# NIC145_Noise_Gate_Schematic.net
KiCad netlist of a schematic drawn in Altium Designer
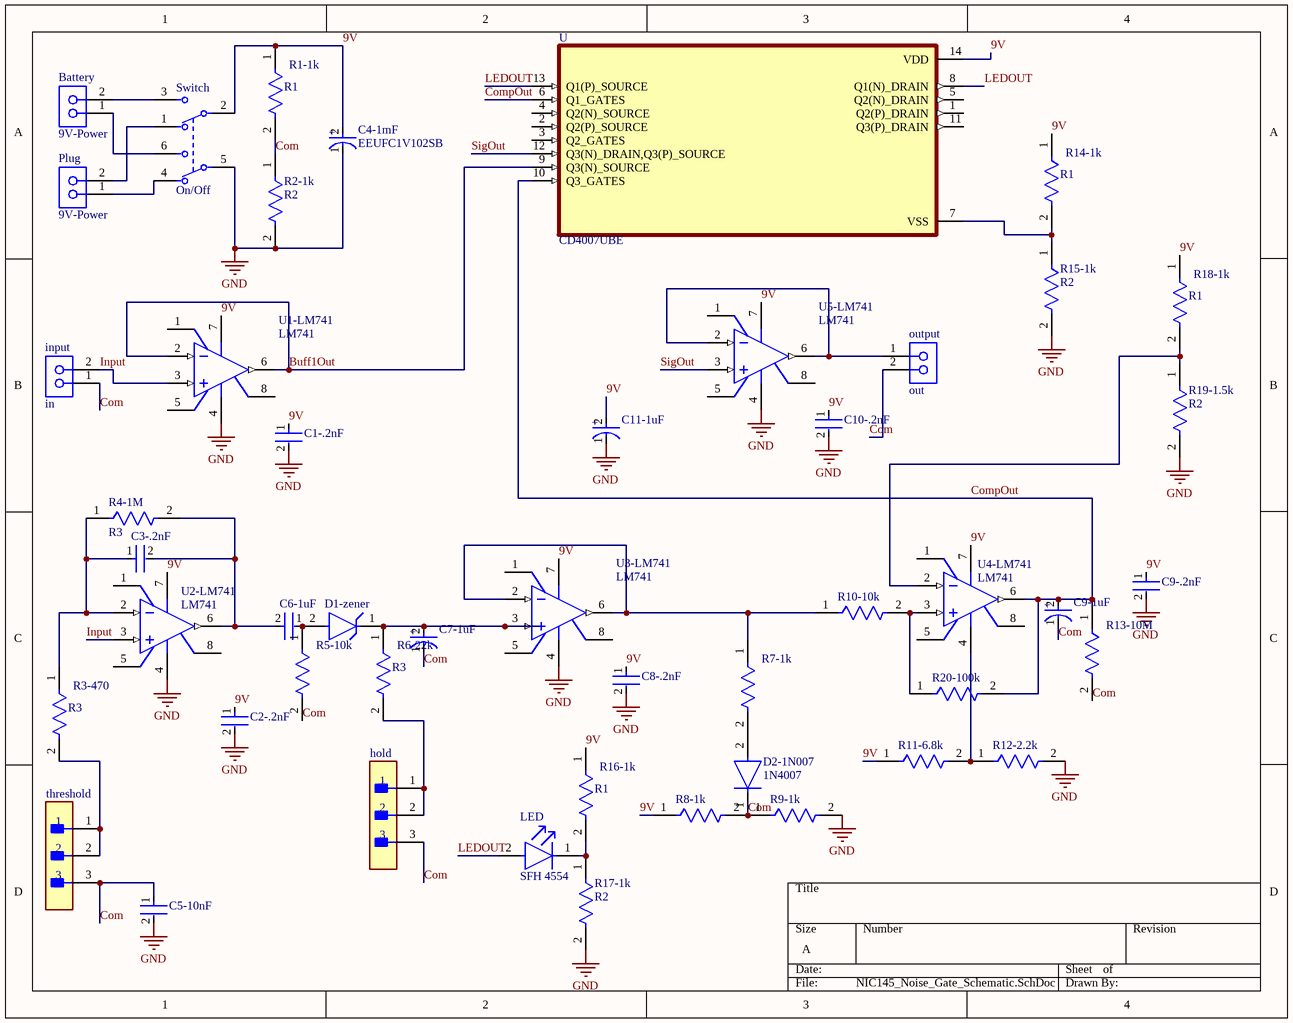
[diagram p0: NIC145_Noise_Gate_Schematic.SchDoc]

(export (version "E")
  (design (tool "Eeschema 10.0.6"))
  (components
    (comp (ref "Battery")
      (value "9V-Power")
      (footprint "SMTC-SSW-102-02-X-S")
      (description "SQ Post Socket, Through-hole, Vertical, -55 to 105 degC, 2.54 mm Pitch, 2-Pin, Female, RoHS")
      (fields (field (name "MANUFACTURER") "Samtec") (field (name "PARTNUMBER") "SSW-102-02-T-S"))
      (libsource (lib "Altium Content Vault") (part "SMTC-SSW-102-02-X-S-X"))
    )
    (comp (ref "C1-.2nF")
      (value "~")
      (footprint "FP-565R30GASS33-MFG")
      (description "565R30GASS33 33nF 3 kV dc Ceramic Single Layer Capacitor; Z5U Dielectric Radial 565R Series")
      (fields (field (name "VOLTAGE") "3kV") (field (name "TOLERANCE") "20%"))
      (libsource (lib "Altium Content Vault") (part "02cd4be3c70576c341d710602a673aa"))
    )
    (comp (ref "C2-.2nF")
      (value "~")
      (footprint "FP-565R30GASS33-MFG")
      (description "565R30GASS33 33nF 3 kV dc Ceramic Single Layer Capacitor; Z5U Dielectric Radial 565R Series")
      (fields (field (name "VOLTAGE") "3kV") (field (name "TOLERANCE") "20%"))
      (libsource (lib "Altium Content Vault") (part "02cd4be3c70576c341d710602a673aa"))
    )
    (comp (ref "C3-.2nF")
      (value "~")
      (footprint "FP-565R30GASS33-MFG")
      (description "565R30GASS33 33nF 3 kV dc Ceramic Single Layer Capacitor; Z5U Dielectric Radial 565R Series")
      (fields (field (name "VOLTAGE") "3kV") (field (name "TOLERANCE") "20%"))
      (libsource (lib "Altium Content Vault") (part "02cd4be3c70576c341d710602a673aa"))
    )
    (comp (ref "C4-1mF")
      (value "EEUFC1V102SB")
      (footprint "FP-RAD-TH-D_16_0_5-L_20_2-MFG")
      (description "Aluminum Electrolytic Capacitors (Radial Lead Type) AEC-Q200 Qualified 1000uF ±20% 35V")
      (fields (field (name "TOLERANCE") "20%"))
      (libsource (lib "Altium Content Vault") (part "203bc49f2ac43e59fd269a8c329ed05"))
    )
    (comp (ref "C5-10nF")
      (value "ECWF4754JL")
      (footprint "FP-ECWF4754JL-MFG")
      (description "CAP FILM 0.75UF 5% 400VDC RADIAL")
      (fields
        (field (name "TOLERANCE") "5%")
        (field (name "OCTOPART") "https://octopart.com/ecw-f4754jl-panasonic-39488642")
      )
      (libsource (lib "Altium Content Vault") (part "b4654b650e69147ec39a6b967a45e02"))
    )
    (comp (ref "C6-1uF")
      (value "PHE844RR7100MR06L2")
      (footprint "FP-PHE844RR7100MR06L2-MFG")
      (description "CAP FILM 1UF 20% 1KVDC RADIAL")
      (fields (field (name "TOLERANCE") "20%"))
      (libsource (lib "Altium Content Vault") (part "236180d848d6139a670b325ea6854c9"))
    )
    (comp (ref "C7-1uF")
      (value "ECA-2CHG010I")
      (footprint "FP-ECA-2CHG010I-MFG")
      (description "CAP ALUM 1UF 20% 160V RADIAL")
      (fields (field (name "TOLERANCE") "20%"))
      (libsource (lib "Altium Content Vault") (part "a00bbbee19879c290e62620ae7e47b1"))
    )
    (comp (ref "C8-.2nF")
      (value "~")
      (footprint "FP-565R30GASS33-MFG")
      (description "565R30GASS33 33nF 3 kV dc Ceramic Single Layer Capacitor; Z5U Dielectric Radial 565R Series")
      (fields (field (name "VOLTAGE") "3kV") (field (name "TOLERANCE") "20%"))
      (libsource (lib "Altium Content Vault") (part "02cd4be3c70576c341d710602a673aa"))
    )
    (comp (ref "C9-.2nF")
      (value "~")
      (footprint "FP-565R30GASS33-MFG")
      (description "565R30GASS33 33nF 3 kV dc Ceramic Single Layer Capacitor; Z5U Dielectric Radial 565R Series")
      (fields (field (name "VOLTAGE") "3kV") (field (name "TOLERANCE") "20%"))
      (libsource (lib "Altium Content Vault") (part "02cd4be3c70576c341d710602a673aa"))
    )
    (comp (ref "C9-1uF")
      (value "ECA-2CHG010I")
      (footprint "FP-ECA-2CHG010I-MFG")
      (description "CAP ALUM 1UF 20% 160V RADIAL")
      (fields (field (name "TOLERANCE") "20%"))
      (libsource (lib "Altium Content Vault") (part "a00bbbee19879c290e62620ae7e47b1"))
    )
    (comp (ref "C10-.2nF")
      (value "~")
      (footprint "FP-565R30GASS33-MFG")
      (description "565R30GASS33 33nF 3 kV dc Ceramic Single Layer Capacitor; Z5U Dielectric Radial 565R Series")
      (fields (field (name "VOLTAGE") "3kV") (field (name "TOLERANCE") "20%"))
      (libsource (lib "Altium Content Vault") (part "02cd4be3c70576c341d710602a673aa"))
    )
    (comp (ref "C11-1uF")
      (value "ECA-2CHG010I")
      (footprint "FP-ECA-2CHG010I-MFG")
      (description "CAP ALUM 1UF 20% 160V RADIAL")
      (fields (field (name "TOLERANCE") "20%"))
      (libsource (lib "Altium Content Vault") (part "a00bbbee19879c290e62620ae7e47b1"))
    )
    (comp (ref "D1-zener")
      (value "1N5242BTR")
      (footprint "FP-017AG-MFG")
      (description "1N5242BTR 1N5242 Series 500 mW 12 V 200 mA Through Hole Zener Diode - DO-35")
      (fields (field (name "TOLERANCE") "5%"))
      (libsource (lib "Altium Content Vault") (part "f813f71cba58e380607f5dd3caf9714"))
    )
    (comp (ref "D2-1N007")
      (value "1N4007")
      (footprint "FP-1N4007-MFG")
      (description "Rectifier diode 1000 V 1 A DO-41, ,")
      (fields
        (field (name "MANUFACTURER") "Diotec")
        (field (name "OCTOPART") "https://octopart.com/1n4007-diotec-4040411")
      )
      (libsource (lib "Altium Content Vault") (part "d7152d700b627762746794eb795d46e"))
    )
    (comp (ref "hold")
      (value "~")
      (footprint "FP-641966-1-MFG")
      (description "CONN HEADER VERT 3POS 6.35MM")
      (fields
        (field (name "MANUFACTURER PART NUMBER") "641966-1")
        (field (name "OCTOPART") "https://octopart.com/641966-1-te+connectivity-46507674")
      )
      (libsource (lib "Altium Content Vault") (part "0d3f023dd272f625e17a2be33dea85f"))
    )
    (comp (ref "input")
      (value "in")
      (footprint "SMTC-SSW-102-02-X-S")
      (description "SQ Post Socket, Through-hole, Vertical, -55 to 105 degC, 2.54 mm Pitch, 2-Pin, Female, RoHS")
      (fields (field (name "MANUFACTURER") "Samtec") (field (name "PARTNUMBER") "SSW-102-02-T-S"))
      (libsource (lib "Altium Content Vault") (part "SMTC-SSW-102-02-X-S-X"))
    )
    (comp (ref "LED")
      (value "SFH 4554")
      (footprint "FP-SFH_4554-MFG")
      (description "EMITTER IR 850NM")
      (fields
        (field (name "OCTOPART") "https://octopart.com/sfh+4554-osram+opto-55819455")
        (field (name "MANUFACTURER") "Osram Opto")
      )
      (libsource (lib "Altium Content Vault") (part "8706943c75ba83719d021d2fdc84c58"))
    )
    (comp (ref "output")
      (value "out")
      (footprint "SMTC-SSW-102-02-X-S")
      (description "SQ Post Socket, Through-hole, Vertical, -55 to 105 degC, 2.54 mm Pitch, 2-Pin, Female, RoHS")
      (fields (field (name "MANUFACTURER") "Samtec") (field (name "PARTNUMBER") "SSW-102-02-T-S"))
      (libsource (lib "Altium Content Vault") (part "SMTC-SSW-102-02-X-S-X"))
    )
    (comp (ref "Plug")
      (value "9V-Power")
      (footprint "SMTC-SSW-102-02-X-S")
      (description "SQ Post Socket, Through-hole, Vertical, -55 to 105 degC, 2.54 mm Pitch, 2-Pin, Female, RoHS")
      (fields (field (name "MANUFACTURER") "Samtec") (field (name "PARTNUMBER") "SSW-102-02-T-S"))
      (libsource (lib "Altium Content Vault") (part "SMTC-SSW-102-02-X-S-X"))
    )
    (comp (ref "R1-1k")
      (value "R1")
      (footprint "FP-MRS25-MFG")
      (description "RES 1K OHM 0.6W 1% AXIAL")
      (fields (field (name "TOLERANCE") "1%"))
      (libsource (lib "Altium Content Vault") (part "1029c3af85768c4190bb7ad29bc67b5"))
    )
    (comp (ref "R2-1k")
      (value "R2")
      (footprint "FP-MRS25-MFG")
      (description "RES 1K OHM 0.6W 1% AXIAL")
      (fields (field (name "TOLERANCE") "1%"))
      (libsource (lib "Altium Content Vault") (part "1029c3af85768c4190bb7ad29bc67b5"))
    )
    (comp (ref "R3-470")
      (value "R3")
      (footprint "FP-MRS25-MFG")
      (description "RES 1K OHM 0.6W 1% AXIAL")
      (fields (field (name "TOLERANCE") "1%"))
      (libsource (lib "Altium Content Vault") (part "1029c3af85768c4190bb7ad29bc67b5"))
    )
    (comp (ref "R4-1M")
      (value "R3")
      (footprint "FP-MRS25-MFG")
      (description "RES 1K OHM 0.6W 1% AXIAL")
      (fields (field (name "TOLERANCE") "1%"))
      (libsource (lib "Altium Content Vault") (part "1029c3af85768c4190bb7ad29bc67b5"))
    )
    (comp (ref "R5-10k")
      (value "R3")
      (footprint "FP-MRS25-MFG")
      (description "RES 1K OHM 0.6W 1% AXIAL")
      (fields (field (name "TOLERANCE") "1%"))
      (libsource (lib "Altium Content Vault") (part "1029c3af85768c4190bb7ad29bc67b5"))
    )
    (comp (ref "R6-22k")
      (value "R3")
      (footprint "FP-MRS25-MFG")
      (description "RES 1K OHM 0.6W 1% AXIAL")
      (fields (field (name "TOLERANCE") "1%"))
      (libsource (lib "Altium Content Vault") (part "1029c3af85768c4190bb7ad29bc67b5"))
    )
    (comp (ref "R7-1k")
      (value "R3")
      (footprint "FP-MRS25-MFG")
      (description "RES 1K OHM 0.6W 1% AXIAL")
      (fields (field (name "TOLERANCE") "1%"))
      (libsource (lib "Altium Content Vault") (part "1029c3af85768c4190bb7ad29bc67b5"))
    )
    (comp (ref "R8-1k")
      (value "R1")
      (footprint "FP-MRS25-MFG")
      (description "RES 1K OHM 0.6W 1% AXIAL")
      (fields (field (name "TOLERANCE") "1%"))
      (libsource (lib "Altium Content Vault") (part "1029c3af85768c4190bb7ad29bc67b5"))
    )
    (comp (ref "R9-1k")
      (value "R2")
      (footprint "FP-MRS25-MFG")
      (description "RES 1K OHM 0.6W 1% AXIAL")
      (fields (field (name "TOLERANCE") "1%"))
      (libsource (lib "Altium Content Vault") (part "1029c3af85768c4190bb7ad29bc67b5"))
    )
    (comp (ref "R10-10k")
      (value "R2")
      (footprint "FP-MRS25-MFG")
      (description "RES 1K OHM 0.6W 1% AXIAL")
      (fields (field (name "TOLERANCE") "1%"))
      (libsource (lib "Altium Content Vault") (part "1029c3af85768c4190bb7ad29bc67b5"))
    )
    (comp (ref "R11-6.8k")
      (value "R1")
      (footprint "FP-MRS25-MFG")
      (description "RES 1K OHM 0.6W 1% AXIAL")
      (fields (field (name "TOLERANCE") "1%"))
      (libsource (lib "Altium Content Vault") (part "1029c3af85768c4190bb7ad29bc67b5"))
    )
    (comp (ref "R12-2.2k")
      (value "R2")
      (footprint "FP-MRS25-MFG")
      (description "RES 1K OHM 0.6W 1% AXIAL")
      (fields (field (name "TOLERANCE") "1%"))
      (libsource (lib "Altium Content Vault") (part "1029c3af85768c4190bb7ad29bc67b5"))
    )
    (comp (ref "R13-10M")
      (value "R3")
      (footprint "FP-MRS25-MFG")
      (description "RES 1K OHM 0.6W 1% AXIAL")
      (fields (field (name "TOLERANCE") "1%"))
      (libsource (lib "Altium Content Vault") (part "1029c3af85768c4190bb7ad29bc67b5"))
    )
    (comp (ref "R14-1k")
      (value "R1")
      (footprint "FP-MRS25-MFG")
      (description "RES 1K OHM 0.6W 1% AXIAL")
      (fields (field (name "TOLERANCE") "1%"))
      (libsource (lib "Altium Content Vault") (part "1029c3af85768c4190bb7ad29bc67b5"))
    )
    (comp (ref "R15-1k")
      (value "R2")
      (footprint "FP-MRS25-MFG")
      (description "RES 1K OHM 0.6W 1% AXIAL")
      (fields (field (name "TOLERANCE") "1%"))
      (libsource (lib "Altium Content Vault") (part "1029c3af85768c4190bb7ad29bc67b5"))
    )
    (comp (ref "R16-1k")
      (value "R1")
      (footprint "FP-MRS25-MFG")
      (description "RES 1K OHM 0.6W 1% AXIAL")
      (fields (field (name "TOLERANCE") "1%"))
      (libsource (lib "Altium Content Vault") (part "1029c3af85768c4190bb7ad29bc67b5"))
    )
    (comp (ref "R17-1k")
      (value "R2")
      (footprint "FP-MRS25-MFG")
      (description "RES 1K OHM 0.6W 1% AXIAL")
      (fields (field (name "TOLERANCE") "1%"))
      (libsource (lib "Altium Content Vault") (part "1029c3af85768c4190bb7ad29bc67b5"))
    )
    (comp (ref "R18-1k")
      (value "R1")
      (footprint "FP-MRS25-MFG")
      (description "RES 1K OHM 0.6W 1% AXIAL")
      (fields (field (name "TOLERANCE") "1%"))
      (libsource (lib "Altium Content Vault") (part "1029c3af85768c4190bb7ad29bc67b5"))
    )
    (comp (ref "R19-1.5k")
      (value "R2")
      (footprint "FP-MRS25-MFG")
      (description "RES 1K OHM 0.6W 1% AXIAL")
      (fields (field (name "TOLERANCE") "1%"))
      (libsource (lib "Altium Content Vault") (part "1029c3af85768c4190bb7ad29bc67b5"))
    )
    (comp (ref "R20-100k")
      (value "R2")
      (footprint "FP-MRS25-MFG")
      (description "RES 1K OHM 0.6W 1% AXIAL")
      (fields (field (name "TOLERANCE") "1%"))
      (libsource (lib "Altium Content Vault") (part "1029c3af85768c4190bb7ad29bc67b5"))
    )
    (comp (ref "Switch")
      (value "On/Off")
      (footprint "FP-100DP1T2B3M2QEH-MFG")
      (description "SWITCH TOGGLE NON ILLUMINATED")
      (fields
        (field (name "MANUFACTURER") "E-Switch")
        (field (name "OCTOPART") "https://octopart.com/100dp1t2b3m2qeh-e-switch-7054946")
      )
      (libsource (lib "Altium Content Vault") (part "0cfc74b8a78428f8f812a73d8c28120"))
    )
    (comp (ref "threshold")
      (value "~")
      (footprint "FP-641966-1-MFG")
      (description "CONN HEADER VERT 3POS 6.35MM")
      (fields
        (field (name "MANUFACTURER PART NUMBER") "641966-1")
        (field (name "OCTOPART") "https://octopart.com/641966-1-te+connectivity-46507674")
      )
      (libsource (lib "Altium Content Vault") (part "0d3f023dd272f625e17a2be33dea85f"))
    )
    (comp (ref "U")
      (value "CD4007UBE")
      (footprint "DIP794W45P254L1969H508Q14")
      (description "CMOS dual complementary pair plus inverter 14-PDIP -55 to 125")
      (fields (field (name "MF") "Texas Instruments"))
      (libsource (lib "CD4007UBE") (part "CD4007UBE"))
    )
    (comp (ref "U1-LM741")
      (value "LM741")
      (footprint "P0008A")
      (description "Operational Amplifier, 8-pin MDIP, Pb-Free")
      (fields (field (name "MANUFACTURER") "Texas Instruments"))
      (libsource (lib "Altium Content Vault") (part "AMP-OPA-LM741-8"))
    )
    (comp (ref "U2-LM741")
      (value "LM741")
      (footprint "P0008A")
      (description "Operational Amplifier, 8-pin MDIP, Pb-Free")
      (fields (field (name "MANUFACTURER") "Texas Instruments"))
      (libsource (lib "Altium Content Vault") (part "AMP-OPA-LM741-8"))
    )
    (comp (ref "U3-LM741")
      (value "LM741")
      (footprint "P0008A")
      (description "Operational Amplifier, 8-pin MDIP, Pb-Free")
      (fields (field (name "MANUFACTURER") "Texas Instruments"))
      (libsource (lib "Altium Content Vault") (part "AMP-OPA-LM741-8"))
    )
    (comp (ref "U4-LM741")
      (value "LM741")
      (footprint "P0008A")
      (description "Operational Amplifier, 8-pin MDIP, Pb-Free")
      (fields (field (name "MANUFACTURER") "Texas Instruments"))
      (libsource (lib "Altium Content Vault") (part "AMP-OPA-LM741-8"))
    )
    (comp (ref "U5-LM741")
      (value "LM741")
      (footprint "P0008A")
      (description "Operational Amplifier, 8-pin MDIP, Pb-Free")
      (fields (field (name "MANUFACTURER") "Texas Instruments"))
      (libsource (lib "Altium Content Vault") (part "AMP-OPA-LM741-8"))
    )
  )
  (nets
    (net (code "1") (name "/9V") (class "Default")
      (node (ref "C1-.2nF") (pin "1") (pinfunction "1_1") (pintype "passive"))
      (node (ref "C10-.2nF") (pin "1") (pinfunction "1_1") (pintype "passive"))
      (node (ref "C11-1uF") (pin "2") (pinfunction "A_2") (pintype "passive"))
      (node (ref "C2-.2nF") (pin "1") (pinfunction "1_1") (pintype "passive"))
      (node (ref "C4-1mF") (pin "2") (pinfunction "A_2") (pintype "passive"))
      (node (ref "C8-.2nF") (pin "1") (pinfunction "1_1") (pintype "passive"))
      (node (ref "C9-.2nF") (pin "1") (pinfunction "1_1") (pintype "passive"))
      (node (ref "R1-1k") (pin "1") (pinfunction "1_1") (pintype "passive"))
      (node (ref "R11-6.8k") (pin "1") (pinfunction "1_1") (pintype "passive"))
      (node (ref "R14-1k") (pin "1") (pinfunction "1_1") (pintype "passive"))
      (node (ref "R16-1k") (pin "1") (pinfunction "1_1") (pintype "passive"))
      (node (ref "R18-1k") (pin "1") (pinfunction "1_1") (pintype "passive"))
      (node (ref "R8-1k") (pin "1") (pinfunction "1_1") (pintype "passive"))
      (node (ref "Switch") (pin "2") (pinfunction "2_2") (pintype "passive"))
      (node (ref "U") (pin "14") (pinfunction "VDD_14") (pintype "power_in"))
      (node (ref "U1-LM741") (pin "7") (pinfunction "V+_7") (pintype "power_in"))
      (node (ref "U2-LM741") (pin "7") (pinfunction "V+_7") (pintype "power_in"))
      (node (ref "U3-LM741") (pin "7") (pinfunction "V+_7") (pintype "power_in"))
      (node (ref "U4-LM741") (pin "7") (pinfunction "V+_7") (pintype "power_in"))
      (node (ref "U5-LM741") (pin "7") (pinfunction "V+_7") (pintype "power_in"))
    )
    (net (code "2") (name "/Buff1Out") (class "Default")
      (node (ref "U") (pin "9") (pinfunction "Q3(N)_SOURCE_9") (pintype "input"))
      (node (ref "U1-LM741") (pin "2") (pinfunction "IN-_2") (pintype "input"))
      (node (ref "U1-LM741") (pin "6") (pinfunction "OUT_6") (pintype "output"))
    )
    (net (code "3") (name "/Com") (class "Default")
      (node (ref "C5-10nF") (pin "1") (pinfunction "1_1") (pintype "passive"))
      (node (ref "C7-1uF") (pin "1") (pinfunction "C_1") (pintype "passive"))
      (node (ref "C9-1uF") (pin "1") (pinfunction "C_1") (pintype "passive"))
      (node (ref "D2-1N007") (pin "1") (pinfunction "C_1") (pintype "passive"))
      (node (ref "R1-1k") (pin "2") (pinfunction "2_2") (pintype "passive"))
      (node (ref "R13-10M") (pin "2") (pinfunction "2_2") (pintype "passive"))
      (node (ref "R2-1k") (pin "1") (pinfunction "1_1") (pintype "passive"))
      (node (ref "R5-10k") (pin "2") (pinfunction "2_2") (pintype "passive"))
      (node (ref "R8-1k") (pin "2") (pinfunction "2_2") (pintype "passive"))
      (node (ref "R9-1k") (pin "1") (pinfunction "1_1") (pintype "passive"))
      (node (ref "hold") (pin "3") (pinfunction "3_3") (pintype "passive"))
      (node (ref "input") (pin "1") (pinfunction "1_1") (pintype "passive"))
      (node (ref "output") (pin "2") (pinfunction "2_2") (pintype "passive"))
      (node (ref "threshold") (pin "3") (pinfunction "3_3") (pintype "passive"))
    )
    (net (code "4") (name "/CompOut") (class "Default")
      (node (ref "C9-1uF") (pin "2") (pinfunction "A_2") (pintype "passive"))
      (node (ref "R13-10M") (pin "1") (pinfunction "1_1") (pintype "passive"))
      (node (ref "R20-100k") (pin "2") (pinfunction "2_2") (pintype "passive"))
      (node (ref "U") (pin "10") (pinfunction "Q3_GATES_10") (pintype "input"))
      (node (ref "U") (pin "6") (pinfunction "Q1_GATES_6") (pintype "input"))
      (node (ref "U4-LM741") (pin "6") (pinfunction "OUT_6") (pintype "output"))
    )
    (net (code "5") (name "/Input") (class "Default")
      (node (ref "U1-LM741") (pin "3") (pinfunction "IN+_3") (pintype "input"))
      (node (ref "U2-LM741") (pin "3") (pinfunction "IN+_3") (pintype "input"))
      (node (ref "input") (pin "2") (pinfunction "2_2") (pintype "passive"))
    )
    (net (code "6") (name "/LEDOUT") (class "Default")
      (node (ref "LED") (pin "2") (pinfunction "A_2") (pintype "passive"))
      (node (ref "U") (pin "13") (pinfunction "Q1(P)_SOURCE_13") (pintype "input"))
      (node (ref "U") (pin "8") (pinfunction "Q1(N)_DRAIN_8") (pintype "output"))
    )
    (net (code "7") (name "/SigOut") (class "Default")
      (node (ref "U") (pin "12") (pinfunction "Q3(N)_DRAIN,Q3(P)_SOURCE_12") (pintype "input"))
      (node (ref "U5-LM741") (pin "3") (pinfunction "IN+_3") (pintype "input"))
    )
    (net (code "8") (name "GND") (class "Default")
      (node (ref "C1-.2nF") (pin "2") (pinfunction "2_2") (pintype "passive"))
      (node (ref "C10-.2nF") (pin "2") (pinfunction "2_2") (pintype "passive"))
      (node (ref "C11-1uF") (pin "1") (pinfunction "C_1") (pintype "passive"))
      (node (ref "C2-.2nF") (pin "2") (pinfunction "2_2") (pintype "passive"))
      (node (ref "C4-1mF") (pin "1") (pinfunction "C_1") (pintype "passive"))
      (node (ref "C5-10nF") (pin "2") (pinfunction "2_2") (pintype "passive"))
      (node (ref "C8-.2nF") (pin "2") (pinfunction "2_2") (pintype "passive"))
      (node (ref "C9-.2nF") (pin "2") (pinfunction "2_2") (pintype "passive"))
      (node (ref "R12-2.2k") (pin "2") (pinfunction "2_2") (pintype "passive"))
      (node (ref "R15-1k") (pin "2") (pinfunction "2_2") (pintype "passive"))
      (node (ref "R17-1k") (pin "2") (pinfunction "2_2") (pintype "passive"))
      (node (ref "R19-1.5k") (pin "2") (pinfunction "2_2") (pintype "passive"))
      (node (ref "R2-1k") (pin "2") (pinfunction "2_2") (pintype "passive"))
      (node (ref "R9-1k") (pin "2") (pinfunction "2_2") (pintype "passive"))
      (node (ref "Switch") (pin "5") (pinfunction "5_5") (pintype "passive"))
      (node (ref "U1-LM741") (pin "4") (pinfunction "V-_4") (pintype "power_in"))
      (node (ref "U2-LM741") (pin "4") (pinfunction "V-_4") (pintype "power_in"))
      (node (ref "U3-LM741") (pin "4") (pinfunction "V-_4") (pintype "power_in"))
      (node (ref "U5-LM741") (pin "4") (pinfunction "V-_4") (pintype "power_in"))
    )
    (net (code "9") (name "Net-(Battery-Pad1)") (class "Default")
      (node (ref "Battery") (pin "1") (pinfunction "1_1") (pintype "passive"))
      (node (ref "Switch") (pin "6") (pinfunction "6_6") (pintype "passive"))
    )
    (net (code "10") (name "Net-(Battery-Pad2)") (class "Default")
      (node (ref "Battery") (pin "2") (pinfunction "2_2") (pintype "passive"))
      (node (ref "Switch") (pin "3") (pinfunction "3_3") (pintype "passive"))
    )
    (net (code "11") (name "Net-(C7-1uF-A)") (class "Default")
      (node (ref "C7-1uF") (pin "2") (pinfunction "A_2") (pintype "passive"))
      (node (ref "D1-zener") (pin "1") (pinfunction "C_1") (pintype "passive"))
      (node (ref "R6-22k") (pin "1") (pinfunction "1_1") (pintype "passive"))
      (node (ref "U3-LM741") (pin "3") (pinfunction "IN+_3") (pintype "input"))
    )
    (net (code "12") (name "Net-(D1-zener-A)") (class "Default")
      (node (ref "C6-1uF") (pin "1") (pinfunction "1_1") (pintype "passive"))
      (node (ref "D1-zener") (pin "2") (pinfunction "A_2") (pintype "passive"))
      (node (ref "R5-10k") (pin "1") (pinfunction "1_1") (pintype "passive"))
    )
    (net (code "13") (name "Net-(D2-1N007-A)") (class "Default")
      (node (ref "D2-1N007") (pin "2") (pinfunction "A_2") (pintype "passive"))
      (node (ref "R7-1k") (pin "2") (pinfunction "2_2") (pintype "passive"))
    )
    (net (code "14") (name "Net-(LED-C)") (class "Default")
      (node (ref "LED") (pin "1") (pinfunction "C_1") (pintype "passive"))
      (node (ref "R16-1k") (pin "2") (pinfunction "2_2") (pintype "passive"))
      (node (ref "R17-1k") (pin "1") (pinfunction "1_1") (pintype "passive"))
    )
    (net (code "15") (name "Net-(Plug-Pad1)") (class "Default")
      (node (ref "Plug") (pin "1") (pinfunction "1_1") (pintype "passive"))
      (node (ref "Switch") (pin "4") (pinfunction "4_4") (pintype "passive"))
    )
    (net (code "16") (name "Net-(Plug-Pad2)") (class "Default")
      (node (ref "Plug") (pin "2") (pinfunction "2_2") (pintype "passive"))
      (node (ref "Switch") (pin "1") (pinfunction "1_1") (pintype "passive"))
    )
    (net (code "17") (name "Net-(R3-470-Pad2)") (class "Default")
      (node (ref "R3-470") (pin "2") (pinfunction "2_2") (pintype "passive"))
      (node (ref "threshold") (pin "1") (pinfunction "1_1") (pintype "passive"))
      (node (ref "threshold") (pin "2") (pinfunction "2_2") (pintype "passive"))
    )
    (net (code "18") (name "Net-(R6-22k-Pad2)") (class "Default")
      (node (ref "R6-22k") (pin "2") (pinfunction "2_2") (pintype "passive"))
      (node (ref "hold") (pin "1") (pinfunction "1_1") (pintype "passive"))
      (node (ref "hold") (pin "2") (pinfunction "2_2") (pintype "passive"))
    )
    (net (code "19") (name "Net-(U-VSS)") (class "Default")
      (node (ref "R14-1k") (pin "2") (pinfunction "2_2") (pintype "passive"))
      (node (ref "R15-1k") (pin "1") (pinfunction "1_1") (pintype "passive"))
      (node (ref "U") (pin "7") (pinfunction "VSS_7") (pintype "power_in"))
    )
    (net (code "20") (name "Net-(U2-LM741-IN-)") (class "Default")
      (node (ref "C3-.2nF") (pin "1") (pinfunction "1_1") (pintype "passive"))
      (node (ref "R3-470") (pin "1") (pinfunction "1_1") (pintype "passive"))
      (node (ref "R4-1M") (pin "1") (pinfunction "1_1") (pintype "passive"))
      (node (ref "U2-LM741") (pin "2") (pinfunction "IN-_2") (pintype "input"))
    )
    (net (code "21") (name "Net-(U2-LM741-OUT)") (class "Default")
      (node (ref "C3-.2nF") (pin "2") (pinfunction "2_2") (pintype "passive"))
      (node (ref "C6-1uF") (pin "2") (pinfunction "2_2") (pintype "passive"))
      (node (ref "R4-1M") (pin "2") (pinfunction "2_2") (pintype "passive"))
      (node (ref "U2-LM741") (pin "6") (pinfunction "OUT_6") (pintype "output"))
    )
    (net (code "22") (name "Net-(U3-LM741-IN-)") (class "Default")
      (node (ref "R10-10k") (pin "1") (pinfunction "1_1") (pintype "passive"))
      (node (ref "R7-1k") (pin "1") (pinfunction "1_1") (pintype "passive"))
      (node (ref "U3-LM741") (pin "2") (pinfunction "IN-_2") (pintype "input"))
      (node (ref "U3-LM741") (pin "6") (pinfunction "OUT_6") (pintype "output"))
    )
    (net (code "23") (name "Net-(U4-LM741-IN+)") (class "Default")
      (node (ref "R10-10k") (pin "2") (pinfunction "2_2") (pintype "passive"))
      (node (ref "R20-100k") (pin "1") (pinfunction "1_1") (pintype "passive"))
      (node (ref "U4-LM741") (pin "3") (pinfunction "IN+_3") (pintype "input"))
    )
    (net (code "24") (name "Net-(U4-LM741-IN-)") (class "Default")
      (node (ref "R18-1k") (pin "2") (pinfunction "2_2") (pintype "passive"))
      (node (ref "R19-1.5k") (pin "1") (pinfunction "1_1") (pintype "passive"))
      (node (ref "U4-LM741") (pin "2") (pinfunction "IN-_2") (pintype "input"))
    )
    (net (code "25") (name "Net-(U4-LM741-V-)") (class "Default")
      (node (ref "R11-6.8k") (pin "2") (pinfunction "2_2") (pintype "passive"))
      (node (ref "R12-2.2k") (pin "1") (pinfunction "1_1") (pintype "passive"))
      (node (ref "U4-LM741") (pin "4") (pinfunction "V-_4") (pintype "power_in"))
    )
    (net (code "26") (name "Net-(U5-LM741-IN-)") (class "Default")
      (node (ref "U5-LM741") (pin "2") (pinfunction "IN-_2") (pintype "input"))
      (node (ref "U5-LM741") (pin "6") (pinfunction "OUT_6") (pintype "output"))
      (node (ref "output") (pin "1") (pinfunction "1_1") (pintype "passive"))
    )
    (net (code "27") (name "unconnected-(U-Q2(N)_DRAIN-Pad5)") (class "Default")
      (node (ref "U") (pin "5") (pinfunction "Q2(N)_DRAIN_5") (pintype "output"))
    )
    (net (code "28") (name "unconnected-(U-Q2(N)_SOURCE-Pad4)") (class "Default")
      (node (ref "U") (pin "4") (pinfunction "Q2(N)_SOURCE_4") (pintype "input"))
    )
    (net (code "29") (name "unconnected-(U-Q2(P)_DRAIN-Pad1)") (class "Default")
      (node (ref "U") (pin "1") (pinfunction "Q2(P)_DRAIN_1") (pintype "output"))
    )
    (net (code "30") (name "unconnected-(U-Q2(P)_SOURCE-Pad2)") (class "Default")
      (node (ref "U") (pin "2") (pinfunction "Q2(P)_SOURCE_2") (pintype "input"))
    )
    (net (code "31") (name "unconnected-(U-Q2_GATES-Pad3)") (class "Default")
      (node (ref "U") (pin "3") (pinfunction "Q2_GATES_3") (pintype "input"))
    )
    (net (code "32") (name "unconnected-(U-Q3(P)_DRAIN-Pad11)") (class "Default")
      (node (ref "U") (pin "11") (pinfunction "Q3(P)_DRAIN_11") (pintype "output"))
    )
    (net (code "33") (name "unconnected-(U1-LM741-NC-Pad8)") (class "Default")
      (node (ref "U1-LM741") (pin "8") (pinfunction "NC_8") (pintype "passive"))
    )
    (net (code "34") (name "unconnected-(U1-LM741-OFS_NULL-Pad1)") (class "Default")
      (node (ref "U1-LM741") (pin "1") (pinfunction "OFS_NULL_1") (pintype "passive"))
    )
    (net (code "35") (name "unconnected-(U1-LM741-OFS_NULL-Pad5)") (class "Default")
      (node (ref "U1-LM741") (pin "5") (pinfunction "OFS_NULL_5") (pintype "passive"))
    )
    (net (code "36") (name "unconnected-(U2-LM741-NC-Pad8)") (class "Default")
      (node (ref "U2-LM741") (pin "8") (pinfunction "NC_8") (pintype "passive"))
    )
    (net (code "37") (name "unconnected-(U2-LM741-OFS_NULL-Pad1)") (class "Default")
      (node (ref "U2-LM741") (pin "1") (pinfunction "OFS_NULL_1") (pintype "passive"))
    )
    (net (code "38") (name "unconnected-(U2-LM741-OFS_NULL-Pad5)") (class "Default")
      (node (ref "U2-LM741") (pin "5") (pinfunction "OFS_NULL_5") (pintype "passive"))
    )
    (net (code "39") (name "unconnected-(U3-LM741-NC-Pad8)") (class "Default")
      (node (ref "U3-LM741") (pin "8") (pinfunction "NC_8") (pintype "passive"))
    )
    (net (code "40") (name "unconnected-(U3-LM741-OFS_NULL-Pad1)") (class "Default")
      (node (ref "U3-LM741") (pin "1") (pinfunction "OFS_NULL_1") (pintype "passive"))
    )
    (net (code "41") (name "unconnected-(U3-LM741-OFS_NULL-Pad5)") (class "Default")
      (node (ref "U3-LM741") (pin "5") (pinfunction "OFS_NULL_5") (pintype "passive"))
    )
    (net (code "42") (name "unconnected-(U4-LM741-NC-Pad8)") (class "Default")
      (node (ref "U4-LM741") (pin "8") (pinfunction "NC_8") (pintype "passive"))
    )
    (net (code "43") (name "unconnected-(U4-LM741-OFS_NULL-Pad1)") (class "Default")
      (node (ref "U4-LM741") (pin "1") (pinfunction "OFS_NULL_1") (pintype "passive"))
    )
    (net (code "44") (name "unconnected-(U4-LM741-OFS_NULL-Pad5)") (class "Default")
      (node (ref "U4-LM741") (pin "5") (pinfunction "OFS_NULL_5") (pintype "passive"))
    )
    (net (code "45") (name "unconnected-(U5-LM741-NC-Pad8)") (class "Default")
      (node (ref "U5-LM741") (pin "8") (pinfunction "NC_8") (pintype "passive"))
    )
    (net (code "46") (name "unconnected-(U5-LM741-OFS_NULL-Pad1)") (class "Default")
      (node (ref "U5-LM741") (pin "1") (pinfunction "OFS_NULL_1") (pintype "passive"))
    )
    (net (code "47") (name "unconnected-(U5-LM741-OFS_NULL-Pad5)") (class "Default")
      (node (ref "U5-LM741") (pin "5") (pinfunction "OFS_NULL_5") (pintype "passive"))
    )
  )
)
